# BMI270.net
KiCad netlist of a schematic drawn in Altium Designer
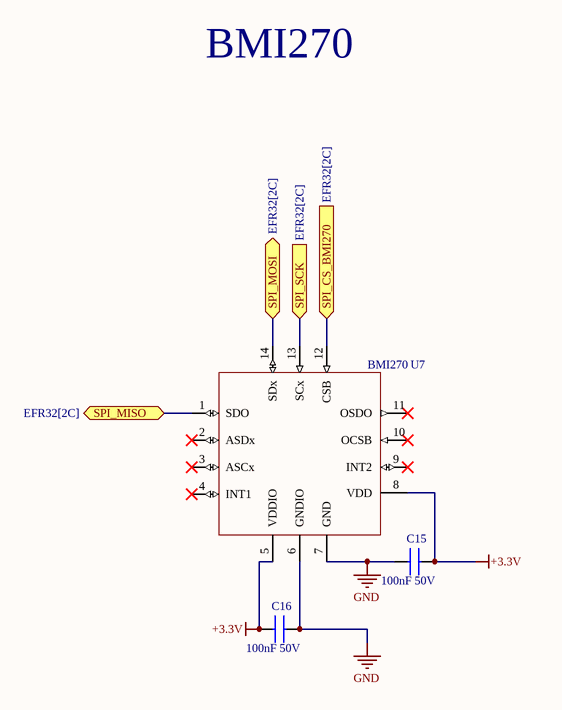
[diagram p0: BMI270.SchDoc]

(export (version "E")
  (design (tool "Eeschema 10.0.6"))
  (components
    (comp (ref "C15")
      (value "100nF 50V")
      (footprint "CAP_0603_1MM")
      (fields
        (field (name "MANUFACTURER") "Yageo")
        (field (name "MANUFACTURER PART NUMBER") "CC0603ZRY5V9BB104")
      )
      (libsource (lib "LPEDT_project_library") (part "CC_0.1uF_0603_ZRY5V9BB104"))
    )
    (comp (ref "C16")
      (value "100nF 50V")
      (footprint "CAP_0603_1MM")
      (fields
        (field (name "MANUFACTURER") "Yageo")
        (field (name "MANUFACTURER PART NUMBER") "CC0603ZRY5V9BB104")
      )
      (libsource (lib "LPEDT_project_library") (part "CC_0.1uF_0603_ZRY5V9BB104"))
    )
    (comp (ref "U7")
      (value "BMI270")
      (footprint "14-QFN_3x2.5_BMI270")
      (description "BMI270 Series 3.6 V 685 µA Smart Ultra-low Power Inertial Measurement Unit")
      (fields (field (name "MANUFACTURER") "Bosch Tools"))
      (libsource (lib "LPEDT_project_library") (part "BMI270"))
    )
  )
  (nets
    (net (code "1") (name "+3.3V") (class "Default")
      (node (ref "C15") (pin "1") (pinfunction "1_1") (pintype "passive"))
      (node (ref "C16") (pin "2") (pinfunction "2_2") (pintype "passive"))
      (node (ref "U7") (pin "5") (pinfunction "VDDIO_5") (pintype "power_in"))
      (node (ref "U7") (pin "8") (pinfunction "VDD_8") (pintype "power_in"))
    )
    (net (code "2") (name "/SPI_CS_BMI270") (class "Default")
      (node (ref "U7") (pin "12") (pinfunction "CSB_12") (pintype "input"))
    )
    (net (code "3") (name "/SPI_MISO") (class "Default")
      (node (ref "U7") (pin "1") (pinfunction "SDO_1") (pintype "bidirectional"))
    )
    (net (code "4") (name "/SPI_MOSI") (class "Default")
      (node (ref "U7") (pin "14") (pinfunction "SDx_14") (pintype "bidirectional"))
    )
    (net (code "5") (name "/SPI_SCK") (class "Default")
      (node (ref "U7") (pin "13") (pinfunction "SCx_13") (pintype "input"))
    )
    (net (code "6") (name "GND") (class "Default")
      (node (ref "C15") (pin "2") (pinfunction "2_2") (pintype "passive"))
      (node (ref "C16") (pin "1") (pinfunction "1_1") (pintype "passive"))
      (node (ref "U7") (pin "6") (pinfunction "GNDIO_6") (pintype "power_in"))
      (node (ref "U7") (pin "7") (pinfunction "GND_7") (pintype "power_in"))
    )
    (net (code "7") (name "unconnected-(U7-ASCx-Pad3)") (class "Default")
      (node (ref "U7") (pin "3") (pinfunction "ASCx_3") (pintype "bidirectional+no_connect"))
    )
    (net (code "8") (name "unconnected-(U7-ASDx-Pad2)") (class "Default")
      (node (ref "U7") (pin "2") (pinfunction "ASDx_2") (pintype "bidirectional+no_connect"))
    )
    (net (code "9") (name "unconnected-(U7-INT1-Pad4)") (class "Default")
      (node (ref "U7") (pin "4") (pinfunction "INT1_4") (pintype "bidirectional+no_connect"))
    )
    (net (code "10") (name "unconnected-(U7-INT2-Pad9)") (class "Default")
      (node (ref "U7") (pin "9") (pinfunction "INT2_9") (pintype "bidirectional+no_connect"))
    )
    (net (code "11") (name "unconnected-(U7-OCSB-Pad10)") (class "Default")
      (node (ref "U7") (pin "10") (pinfunction "OCSB_10") (pintype "input+no_connect"))
    )
    (net (code "12") (name "unconnected-(U7-OSDO-Pad11)") (class "Default")
      (node (ref "U7") (pin "11") (pinfunction "OSDO_11") (pintype "output+no_connect"))
    )
  )
)
